# lifetile.net
KiCad netlist of a schematic drawn in EAGLE
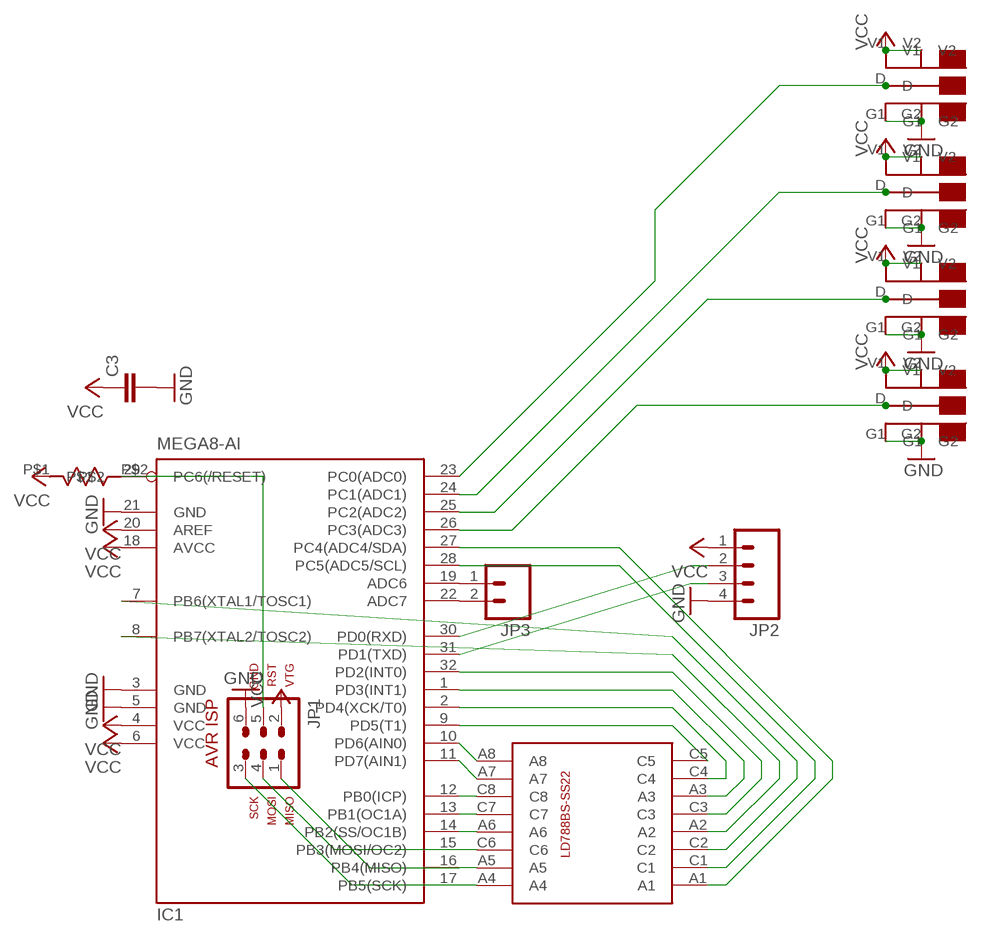
[diagram p0: schematic, sheet 1]

(export (version "E")
  (design (tool "Eeschema 10.0.6"))
  (components
    (comp (ref "C3")
      (value "CAPKIT")
      (footprint "eagle-import:CAP-PTH-SMALL-KIT")
      (libsource (lib "eagle-import") (part "CAPKIT"))
    )
    (comp (ref "IC1")
      (value "MEGA8-AI")
      (footprint "eagle-import:TQFP32-08")
      (fields (field (name "MPN") "ATMEGA8-16AU"))
      (libsource (lib "eagle-import") (part "MEGA8-AI"))
    )
    (comp (ref "JP1")
      (value "AVR-ISP-6")
      (footprint "eagle-import:AVR-ISP-6")
      (libsource (lib "eagle-import") (part "AVR-ISP-6"))
    )
    (comp (ref "JP2")
      (value "M04LOCK")
      (footprint "eagle-import:1X04_LOCK")
      (libsource (lib "eagle-import") (part "M04LOCK"))
    )
    (comp (ref "JP3")
      (value "M02PTH")
      (footprint "eagle-import:1X02")
      (libsource (lib "eagle-import") (part "M02PTH"))
    )
    (comp (ref "U$1")
      (value "LD-1088BS")
      (footprint "eagle-import:LD-1088BS")
      (libsource (lib "eagle-import") (part "LD-1088BS"))
    )
    (comp (ref "U$2")
      (value "R-7")
      (footprint "eagle-import:R-7")
      (libsource (lib "eagle-import") (part "R-7"))
    )
    (comp (ref "U$4")
      (value "EDGE_5_PTH")
      (footprint "eagle-import:EDGE_5_SMT_PTH")
      (libsource (lib "eagle-import") (part "EDGE_5_PTH"))
    )
    (comp (ref "U$5")
      (value "EDGE_5_PTH")
      (footprint "eagle-import:EDGE_5_SMT_PTH")
      (libsource (lib "eagle-import") (part "EDGE_5_PTH"))
    )
    (comp (ref "U$6")
      (value "EDGE_5_PTH")
      (footprint "eagle-import:EDGE_5_SMT_PTH")
      (libsource (lib "eagle-import") (part "EDGE_5_PTH"))
    )
    (comp (ref "U$11")
      (value "EDGE_5_PTH")
      (footprint "eagle-import:EDGE_5_SMT_PTH")
      (libsource (lib "eagle-import") (part "EDGE_5_PTH"))
    )
  )
  (nets
    (net (code "1") (name "GND") (class "Default")
      (node (ref "C3") (pin "2") (pinfunction "2_2") (pintype "passive"))
      (node (ref "IC1") (pin "21") (pinfunction "GND_21") (pintype "power_in"))
      (node (ref "IC1") (pin "3") (pinfunction "GND_3") (pintype "power_in"))
      (node (ref "IC1") (pin "5") (pinfunction "GND_5") (pintype "power_in"))
      (node (ref "JP1") (pin "6") (pinfunction "6_6") (pintype "passive"))
      (node (ref "JP2") (pin "4") (pinfunction "4_4") (pintype "passive"))
      (node (ref "U$11") (pin "G1") (pinfunction "G1_G1") (pintype "bidirectional"))
      (node (ref "U$11") (pin "G2") (pinfunction "G2_G2") (pintype "bidirectional"))
      (node (ref "U$4") (pin "G1") (pinfunction "G1_G1") (pintype "bidirectional"))
      (node (ref "U$4") (pin "G2") (pinfunction "G2_G2") (pintype "bidirectional"))
      (node (ref "U$5") (pin "G1") (pinfunction "G1_G1") (pintype "bidirectional"))
      (node (ref "U$5") (pin "G2") (pinfunction "G2_G2") (pintype "bidirectional"))
      (node (ref "U$6") (pin "G1") (pinfunction "G1_G1") (pintype "bidirectional"))
      (node (ref "U$6") (pin "G2") (pinfunction "G2_G2") (pintype "bidirectional"))
    )
    (net (code "2") (name "Net-(IC1-ADC6)") (class "Default")
      (node (ref "IC1") (pin "19") (pinfunction "ADC6_19") (pintype "bidirectional"))
      (node (ref "JP3") (pin "1") (pinfunction "1_1") (pintype "passive"))
    )
    (net (code "3") (name "Net-(IC1-ADC7)") (class "Default")
      (node (ref "IC1") (pin "22") (pinfunction "ADC7_22") (pintype "bidirectional"))
      (node (ref "JP3") (pin "2") (pinfunction "2_2") (pintype "passive"))
    )
    (net (code "4") (name "Net-(IC1-PB0(ICP))") (class "Default")
      (node (ref "IC1") (pin "12") (pinfunction "PB0(ICP)_12") (pintype "bidirectional"))
      (node (ref "U$1") (pin "C8") (pinfunction "C8_C8") (pintype "bidirectional"))
    )
    (net (code "5") (name "Net-(IC1-PB1(OC1A))") (class "Default")
      (node (ref "IC1") (pin "13") (pinfunction "PB1(OC1A)_13") (pintype "bidirectional"))
      (node (ref "U$1") (pin "C7") (pinfunction "C7_C7") (pintype "bidirectional"))
    )
    (net (code "6") (name "Net-(IC1-PB2(SS{slash}OC1B))") (class "Default")
      (node (ref "IC1") (pin "14") (pinfunction "PB2(SS/OC1B)_14") (pintype "bidirectional"))
      (node (ref "U$1") (pin "A6") (pinfunction "A6_A6") (pintype "bidirectional"))
    )
    (net (code "7") (name "Net-(IC1-PB3(MOSI{slash}OC2))") (class "Default")
      (node (ref "IC1") (pin "15") (pinfunction "PB3(MOSI/OC2)_15") (pintype "bidirectional"))
      (node (ref "JP1") (pin "4") (pinfunction "4_4") (pintype "passive"))
      (node (ref "U$1") (pin "C6") (pinfunction "C6_C6") (pintype "bidirectional"))
    )
    (net (code "8") (name "Net-(IC1-PB4(MISO))") (class "Default")
      (node (ref "IC1") (pin "16") (pinfunction "PB4(MISO)_16") (pintype "bidirectional"))
      (node (ref "JP1") (pin "1") (pinfunction "1_1") (pintype "passive"))
      (node (ref "U$1") (pin "A5") (pinfunction "A5_A5") (pintype "bidirectional"))
    )
    (net (code "9") (name "Net-(IC1-PB5(SCK))") (class "Default")
      (node (ref "IC1") (pin "17") (pinfunction "PB5(SCK)_17") (pintype "bidirectional"))
      (node (ref "JP1") (pin "3") (pinfunction "3_3") (pintype "passive"))
      (node (ref "U$1") (pin "A4") (pinfunction "A4_A4") (pintype "bidirectional"))
    )
    (net (code "10") (name "Net-(IC1-PB6(XTAL1{slash}TOSC1))") (class "Default")
      (node (ref "IC1") (pin "7") (pinfunction "PB6(XTAL1/TOSC1)_7") (pintype "bidirectional"))
      (node (ref "U$1") (pin "C2") (pinfunction "C2_C2") (pintype "bidirectional"))
    )
    (net (code "11") (name "Net-(IC1-PB7(XTAL2{slash}TOSC2))") (class "Default")
      (node (ref "IC1") (pin "8") (pinfunction "PB7(XTAL2/TOSC2)_8") (pintype "bidirectional"))
      (node (ref "U$1") (pin "A2") (pinfunction "A2_A2") (pintype "bidirectional"))
    )
    (net (code "12") (name "Net-(IC1-PC0(ADC0))") (class "Default")
      (node (ref "IC1") (pin "23") (pinfunction "PC0(ADC0)_23") (pintype "bidirectional"))
      (node (ref "U$11") (pin "D") (pinfunction "D_D") (pintype "bidirectional"))
    )
    (net (code "13") (name "Net-(IC1-PC1(ADC1))") (class "Default")
      (node (ref "IC1") (pin "24") (pinfunction "PC1(ADC1)_24") (pintype "bidirectional"))
      (node (ref "U$6") (pin "D") (pinfunction "D_D") (pintype "bidirectional"))
    )
    (net (code "14") (name "Net-(IC1-PC2(ADC2))") (class "Default")
      (node (ref "IC1") (pin "25") (pinfunction "PC2(ADC2)_25") (pintype "bidirectional"))
      (node (ref "U$5") (pin "D") (pinfunction "D_D") (pintype "bidirectional"))
    )
    (net (code "15") (name "Net-(IC1-PC3(ADC3))") (class "Default")
      (node (ref "IC1") (pin "26") (pinfunction "PC3(ADC3)_26") (pintype "bidirectional"))
      (node (ref "U$4") (pin "D") (pinfunction "D_D") (pintype "bidirectional"))
    )
    (net (code "16") (name "Net-(IC1-PC4(ADC4{slash}SDA))") (class "Default")
      (node (ref "IC1") (pin "27") (pinfunction "PC4(ADC4/SDA)_27") (pintype "bidirectional"))
      (node (ref "U$1") (pin "A1") (pinfunction "A1_A1") (pintype "bidirectional"))
    )
    (net (code "17") (name "Net-(IC1-PC5(ADC5{slash}SCL))") (class "Default")
      (node (ref "IC1") (pin "28") (pinfunction "PC5(ADC5/SCL)_28") (pintype "bidirectional"))
      (node (ref "U$1") (pin "C1") (pinfunction "C1_C1") (pintype "bidirectional"))
    )
    (net (code "18") (name "Net-(IC1-PC6({slash}RESET))") (class "Default")
      (node (ref "IC1") (pin "29") (pinfunction "PC6(/RESET)_29") (pintype "bidirectional"))
      (node (ref "JP1") (pin "5") (pinfunction "5_5") (pintype "passive"))
      (node (ref "U$2") (pin "P$2") (pinfunction "P$2_P$2") (pintype "bidirectional"))
    )
    (net (code "19") (name "Net-(IC1-PD0(RXD))") (class "Default")
      (node (ref "IC1") (pin "30") (pinfunction "PD0(RXD)_30") (pintype "bidirectional"))
      (node (ref "JP2") (pin "2") (pinfunction "2_2") (pintype "passive"))
    )
    (net (code "20") (name "Net-(IC1-PD1(TXD))") (class "Default")
      (node (ref "IC1") (pin "31") (pinfunction "PD1(TXD)_31") (pintype "bidirectional"))
      (node (ref "JP2") (pin "3") (pinfunction "3_3") (pintype "passive"))
    )
    (net (code "21") (name "Net-(IC1-PD2(INT0))") (class "Default")
      (node (ref "IC1") (pin "32") (pinfunction "PD2(INT0)_32") (pintype "bidirectional"))
      (node (ref "U$1") (pin "C3") (pinfunction "C3_C3") (pintype "bidirectional"))
    )
    (net (code "22") (name "Net-(IC1-PD3(INT1))") (class "Default")
      (node (ref "IC1") (pin "1") (pinfunction "PD3(INT1)_1") (pintype "bidirectional"))
      (node (ref "U$1") (pin "A3") (pinfunction "A3_A3") (pintype "bidirectional"))
    )
    (net (code "23") (name "Net-(IC1-PD4(XCK{slash}T0))") (class "Default")
      (node (ref "IC1") (pin "2") (pinfunction "PD4(XCK/T0)_2") (pintype "bidirectional"))
      (node (ref "U$1") (pin "C4") (pinfunction "C4_C4") (pintype "bidirectional"))
    )
    (net (code "24") (name "Net-(IC1-PD5(T1))") (class "Default")
      (node (ref "IC1") (pin "9") (pinfunction "PD5(T1)_9") (pintype "bidirectional"))
      (node (ref "U$1") (pin "C5") (pinfunction "C5_C5") (pintype "bidirectional"))
    )
    (net (code "25") (name "Net-(IC1-PD6(AIN0))") (class "Default")
      (node (ref "IC1") (pin "10") (pinfunction "PD6(AIN0)_10") (pintype "bidirectional"))
      (node (ref "U$1") (pin "A8") (pinfunction "A8_A8") (pintype "bidirectional"))
    )
    (net (code "26") (name "Net-(IC1-PD7(AIN1))") (class "Default")
      (node (ref "IC1") (pin "11") (pinfunction "PD7(AIN1)_11") (pintype "bidirectional"))
      (node (ref "U$1") (pin "A7") (pinfunction "A7_A7") (pintype "bidirectional"))
    )
    (net (code "27") (name "VCC") (class "Default")
      (node (ref "C3") (pin "1") (pinfunction "1_1") (pintype "passive"))
      (node (ref "IC1") (pin "18") (pinfunction "AVCC_18") (pintype "power_in"))
      (node (ref "IC1") (pin "20") (pinfunction "AREF_20") (pintype "passive"))
      (node (ref "IC1") (pin "4") (pinfunction "VCC_4") (pintype "power_in"))
      (node (ref "IC1") (pin "6") (pinfunction "VCC_6") (pintype "power_in"))
      (node (ref "JP1") (pin "2") (pinfunction "2_2") (pintype "passive"))
      (node (ref "JP2") (pin "1") (pinfunction "1_1") (pintype "passive"))
      (node (ref "U$11") (pin "V1") (pinfunction "V1_V1") (pintype "bidirectional"))
      (node (ref "U$11") (pin "V2") (pinfunction "V2_V2") (pintype "bidirectional"))
      (node (ref "U$2") (pin "P$1") (pinfunction "P$1_P$1") (pintype "bidirectional"))
      (node (ref "U$4") (pin "V1") (pinfunction "V1_V1") (pintype "bidirectional"))
      (node (ref "U$4") (pin "V2") (pinfunction "V2_V2") (pintype "bidirectional"))
      (node (ref "U$5") (pin "V1") (pinfunction "V1_V1") (pintype "bidirectional"))
      (node (ref "U$5") (pin "V2") (pinfunction "V2_V2") (pintype "bidirectional"))
      (node (ref "U$6") (pin "V1") (pinfunction "V1_V1") (pintype "bidirectional"))
      (node (ref "U$6") (pin "V2") (pinfunction "V2_V2") (pintype "bidirectional"))
    )
  )
)
